# BQ25504v2.net
KiCad netlist of a schematic drawn in Altium Designer
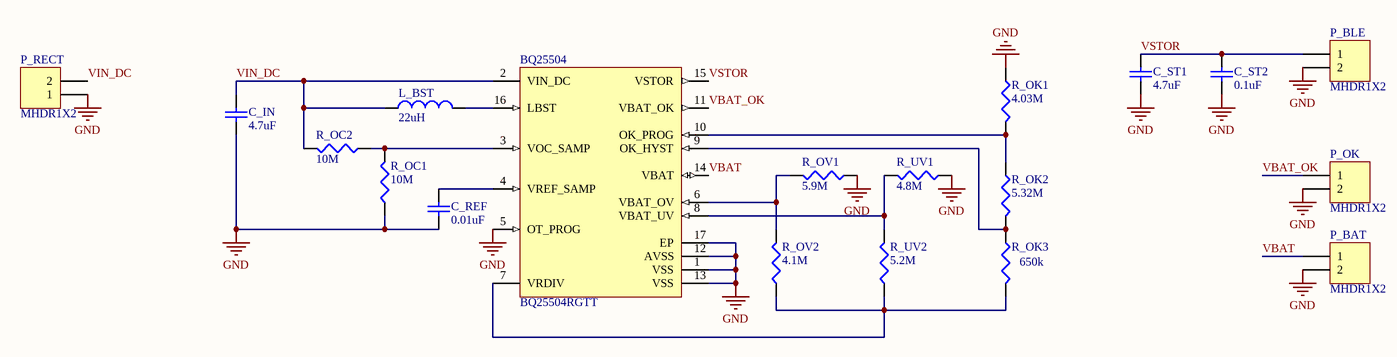
[diagram p0: BQ25504v2.SchDoc]

(export (version "E")
  (design (tool "Eeschema 10.0.6"))
  (components
    (comp (ref "BQ25504")
      (value "BQ25504RGTT")
      (footprint "RGT0016C_V")
      (fields (field (name "MANUFACTURER") "Texas Instruments"))
      (libsource (lib "Altium Content Vault") (part "TI-BQ25504RGT16-1700X1700TP"))
    )
    (comp (ref "C_IN")
      (value "4.7uF")
      (footprint "0402")
      (description "Capacitor (Semiconductor SIM Model)")
      (fields (field (name "Comment") "Cap Semi") (field (name "PUBLISHER") "Altium Limited"))
      (libsource (lib "Miscellaneous Devices") (part "Cap Semi"))
    )
    (comp (ref "C_REF")
      (value "0.01uF")
      (footprint "0402")
      (description "Capacitor (Semiconductor SIM Model)")
      (fields (field (name "Comment") "Cap Semi") (field (name "PUBLISHER") "Altium Limited"))
      (libsource (lib "Miscellaneous Devices") (part "Cap Semi"))
    )
    (comp (ref "C_ST1")
      (value "4.7uF")
      (footprint "0402")
      (description "Capacitor (Semiconductor SIM Model)")
      (fields (field (name "Comment") "Cap Semi") (field (name "PUBLISHER") "Altium Limited"))
      (libsource (lib "Miscellaneous Devices") (part "Cap Semi"))
    )
    (comp (ref "C_ST2")
      (value "0.1uF")
      (footprint "0402")
      (description "Capacitor (Semiconductor SIM Model)")
      (fields (field (name "Comment") "Cap Semi") (field (name "PUBLISHER") "Altium Limited"))
      (libsource (lib "Miscellaneous Devices") (part "Cap Semi"))
    )
    (comp (ref "L_BST")
      (value "22uH")
      (footprint "0402-A")
      (description "Inductor")
      (fields (field (name "PUBLISHER") "Altium Limited"))
      (libsource (lib "Miscellaneous Devices") (part "Inductor"))
    )
    (comp (ref "P_BAT")
      (value "MHDR1X2")
      (footprint "MHDR1X2")
      (description "Header, 2-Pin")
      (fields (field (name "PUBLISHER") "Altium Limited"))
      (libsource (lib "") (part "MHDR1X2_1"))
    )
    (comp (ref "P_BLE")
      (value "MHDR1X2")
      (footprint "MHDR1X2")
      (description "Header, 2-Pin")
      (fields (field (name "PUBLISHER") "Altium Limited"))
      (libsource (lib "") (part "MHDR1X2_1"))
    )
    (comp (ref "P_OK")
      (value "MHDR1X2")
      (footprint "MHDR1X2")
      (description "Header, 2-Pin")
      (fields (field (name "PUBLISHER") "Altium Limited"))
      (libsource (lib "") (part "MHDR1X2_1"))
    )
    (comp (ref "P_RECT")
      (value "MHDR1X2")
      (footprint "MHDR1X2")
      (description "Header, 2-Pin")
      (fields (field (name "PUBLISHER") "Altium Limited"))
      (libsource (lib "Miscellaneous Connectors") (part "MHDR1X2"))
    )
    (comp (ref "R_OC1")
      (value "10M")
      (footprint "12Z-2010")
      (description "Resistor")
      (fields (field (name "Comment") "Res3") (field (name "PUBLISHER") "Altium Limited"))
      (libsource (lib "Miscellaneous Devices") (part "Res3"))
    )
    (comp (ref "R_OC2")
      (value "10M")
      (footprint "12Z-2010")
      (description "Resistor")
      (fields (field (name "Comment") "Res3") (field (name "PUBLISHER") "Altium Limited"))
      (libsource (lib "Miscellaneous Devices") (part "Res3"))
    )
    (comp (ref "R_OK1")
      (value "4.03M")
      (footprint "12Z-2010")
      (description "Resistor")
      (fields (field (name "Comment") "Res3") (field (name "PUBLISHER") "Altium Limited"))
      (libsource (lib "Miscellaneous Devices") (part "Res3"))
    )
    (comp (ref "R_OK2")
      (value "5.32M")
      (footprint "12Z-2010")
      (description "Resistor")
      (fields (field (name "Comment") "Res3") (field (name "PUBLISHER") "Altium Limited"))
      (libsource (lib "Miscellaneous Devices") (part "Res3"))
    )
    (comp (ref "R_OK3")
      (value "650k")
      (footprint "12Z-2010")
      (description "Resistor")
      (fields (field (name "Comment") "Res3") (field (name "PUBLISHER") "Altium Limited"))
      (libsource (lib "Miscellaneous Devices") (part "Res3"))
    )
    (comp (ref "R_OV1")
      (value "5.9M")
      (footprint "12Z-2010")
      (description "Resistor")
      (fields (field (name "Comment") "Res3") (field (name "PUBLISHER") "Altium Limited"))
      (libsource (lib "Miscellaneous Devices") (part "Res3"))
    )
    (comp (ref "R_OV2")
      (value "4.1M")
      (footprint "12Z-2010")
      (description "Resistor")
      (fields (field (name "Comment") "Res3") (field (name "PUBLISHER") "Altium Limited"))
      (libsource (lib "Miscellaneous Devices") (part "Res3"))
    )
    (comp (ref "R_UV1")
      (value "4.8M")
      (footprint "12Z-2010")
      (description "Resistor")
      (fields (field (name "Comment") "Res3") (field (name "PUBLISHER") "Altium Limited"))
      (libsource (lib "Miscellaneous Devices") (part "Res3"))
    )
    (comp (ref "R_UV2")
      (value "5.2M")
      (footprint "12Z-2010")
      (description "Resistor")
      (fields (field (name "Comment") "Res3") (field (name "PUBLISHER") "Altium Limited"))
      (libsource (lib "Miscellaneous Devices") (part "Res3"))
    )
  )
  (nets
    (net (code "1") (name "/VBAT") (class "Default")
      (node (ref "BQ25504") (pin "14") (pinfunction "VBAT_14") (pintype "bidirectional"))
      (node (ref "P_BAT") (pin "1") (pinfunction "1_1") (pintype "passive"))
    )
    (net (code "2") (name "/VBAT_OK") (class "Default")
      (node (ref "BQ25504") (pin "11") (pinfunction "VBAT_OK_11") (pintype "output"))
      (node (ref "P_OK") (pin "1") (pinfunction "1_1") (pintype "passive"))
    )
    (net (code "3") (name "/VIN_DC") (class "Default")
      (node (ref "BQ25504") (pin "2") (pinfunction "VIN_DC_2") (pintype "power_in"))
      (node (ref "C_IN") (pin "2") (pinfunction "2_2") (pintype "passive"))
      (node (ref "L_BST") (pin "1") (pinfunction "1_1") (pintype "passive"))
      (node (ref "P_RECT") (pin "2") (pinfunction "2_2") (pintype "passive"))
      (node (ref "R_OC2") (pin "2") (pinfunction "2_2") (pintype "passive"))
    )
    (net (code "4") (name "/VSTOR") (class "Default")
      (node (ref "BQ25504") (pin "15") (pinfunction "VSTOR_15") (pintype "output"))
      (node (ref "C_ST1") (pin "2") (pinfunction "2_2") (pintype "passive"))
      (node (ref "C_ST2") (pin "2") (pinfunction "2_2") (pintype "passive"))
      (node (ref "P_BLE") (pin "1") (pinfunction "1_1") (pintype "passive"))
    )
    (net (code "5") (name "GND") (class "Default")
      (node (ref "BQ25504") (pin "1") (pinfunction "VSS_1") (pintype "power_in"))
      (node (ref "BQ25504") (pin "12") (pinfunction "AVSS_12") (pintype "power_in"))
      (node (ref "BQ25504") (pin "13") (pinfunction "VSS_13") (pintype "power_in"))
      (node (ref "BQ25504") (pin "17") (pinfunction "EP_17") (pintype "passive"))
      (node (ref "BQ25504") (pin "5") (pinfunction "OT_PROG_5") (pintype "input"))
      (node (ref "C_IN") (pin "1") (pinfunction "1_1") (pintype "passive"))
      (node (ref "C_REF") (pin "1") (pinfunction "1_1") (pintype "passive"))
      (node (ref "C_ST1") (pin "1") (pinfunction "1_1") (pintype "passive"))
      (node (ref "C_ST2") (pin "1") (pinfunction "1_1") (pintype "passive"))
      (node (ref "P_BAT") (pin "2") (pinfunction "2_2") (pintype "passive"))
      (node (ref "P_BLE") (pin "2") (pinfunction "2_2") (pintype "passive"))
      (node (ref "P_OK") (pin "2") (pinfunction "2_2") (pintype "passive"))
      (node (ref "P_RECT") (pin "1") (pinfunction "1_1") (pintype "passive"))
      (node (ref "R_OC1") (pin "1") (pinfunction "1_1") (pintype "passive"))
      (node (ref "R_OK1") (pin "1") (pinfunction "1_1") (pintype "passive"))
      (node (ref "R_OV1") (pin "1") (pinfunction "1_1") (pintype "passive"))
      (node (ref "R_UV1") (pin "1") (pinfunction "1_1") (pintype "passive"))
    )
    (net (code "6") (name "Net-(BQ25504-LBST)") (class "Default")
      (node (ref "BQ25504") (pin "16") (pinfunction "LBST_16") (pintype "input"))
      (node (ref "L_BST") (pin "2") (pinfunction "2_2") (pintype "passive"))
    )
    (net (code "7") (name "Net-(BQ25504-OK_HYST)") (class "Default")
      (node (ref "BQ25504") (pin "9") (pinfunction "OK_HYST_9") (pintype "input"))
      (node (ref "R_OK2") (pin "2") (pinfunction "2_2") (pintype "passive"))
      (node (ref "R_OK3") (pin "1") (pinfunction "1_1") (pintype "passive"))
    )
    (net (code "8") (name "Net-(BQ25504-OK_PROG)") (class "Default")
      (node (ref "BQ25504") (pin "10") (pinfunction "OK_PROG_10") (pintype "input"))
      (node (ref "R_OK1") (pin "2") (pinfunction "2_2") (pintype "passive"))
      (node (ref "R_OK2") (pin "1") (pinfunction "1_1") (pintype "passive"))
    )
    (net (code "9") (name "Net-(BQ25504-VBAT_OV)") (class "Default")
      (node (ref "BQ25504") (pin "6") (pinfunction "VBAT_OV_6") (pintype "input"))
      (node (ref "R_OV1") (pin "2") (pinfunction "2_2") (pintype "passive"))
      (node (ref "R_OV2") (pin "2") (pinfunction "2_2") (pintype "passive"))
    )
    (net (code "10") (name "Net-(BQ25504-VBAT_UV)") (class "Default")
      (node (ref "BQ25504") (pin "8") (pinfunction "VBAT_UV_8") (pintype "input"))
      (node (ref "R_UV1") (pin "2") (pinfunction "2_2") (pintype "passive"))
      (node (ref "R_UV2") (pin "2") (pinfunction "2_2") (pintype "passive"))
    )
    (net (code "11") (name "Net-(BQ25504-VOC_SAMP)") (class "Default")
      (node (ref "BQ25504") (pin "3") (pinfunction "VOC_SAMP_3") (pintype "input"))
      (node (ref "R_OC1") (pin "2") (pinfunction "2_2") (pintype "passive"))
      (node (ref "R_OC2") (pin "1") (pinfunction "1_1") (pintype "passive"))
    )
    (net (code "12") (name "Net-(BQ25504-VRDIV)") (class "Default")
      (node (ref "BQ25504") (pin "7") (pinfunction "VRDIV_7") (pintype "power_in"))
      (node (ref "R_OK3") (pin "2") (pinfunction "2_2") (pintype "passive"))
      (node (ref "R_OV2") (pin "1") (pinfunction "1_1") (pintype "passive"))
      (node (ref "R_UV2") (pin "1") (pinfunction "1_1") (pintype "passive"))
    )
    (net (code "13") (name "Net-(BQ25504-VREF_SAMP)") (class "Default")
      (node (ref "BQ25504") (pin "4") (pinfunction "VREF_SAMP_4") (pintype "input"))
      (node (ref "C_REF") (pin "2") (pinfunction "2_2") (pintype "passive"))
    )
  )
)
